# working.net
KiCad netlist of a schematic drawn in EAGLE
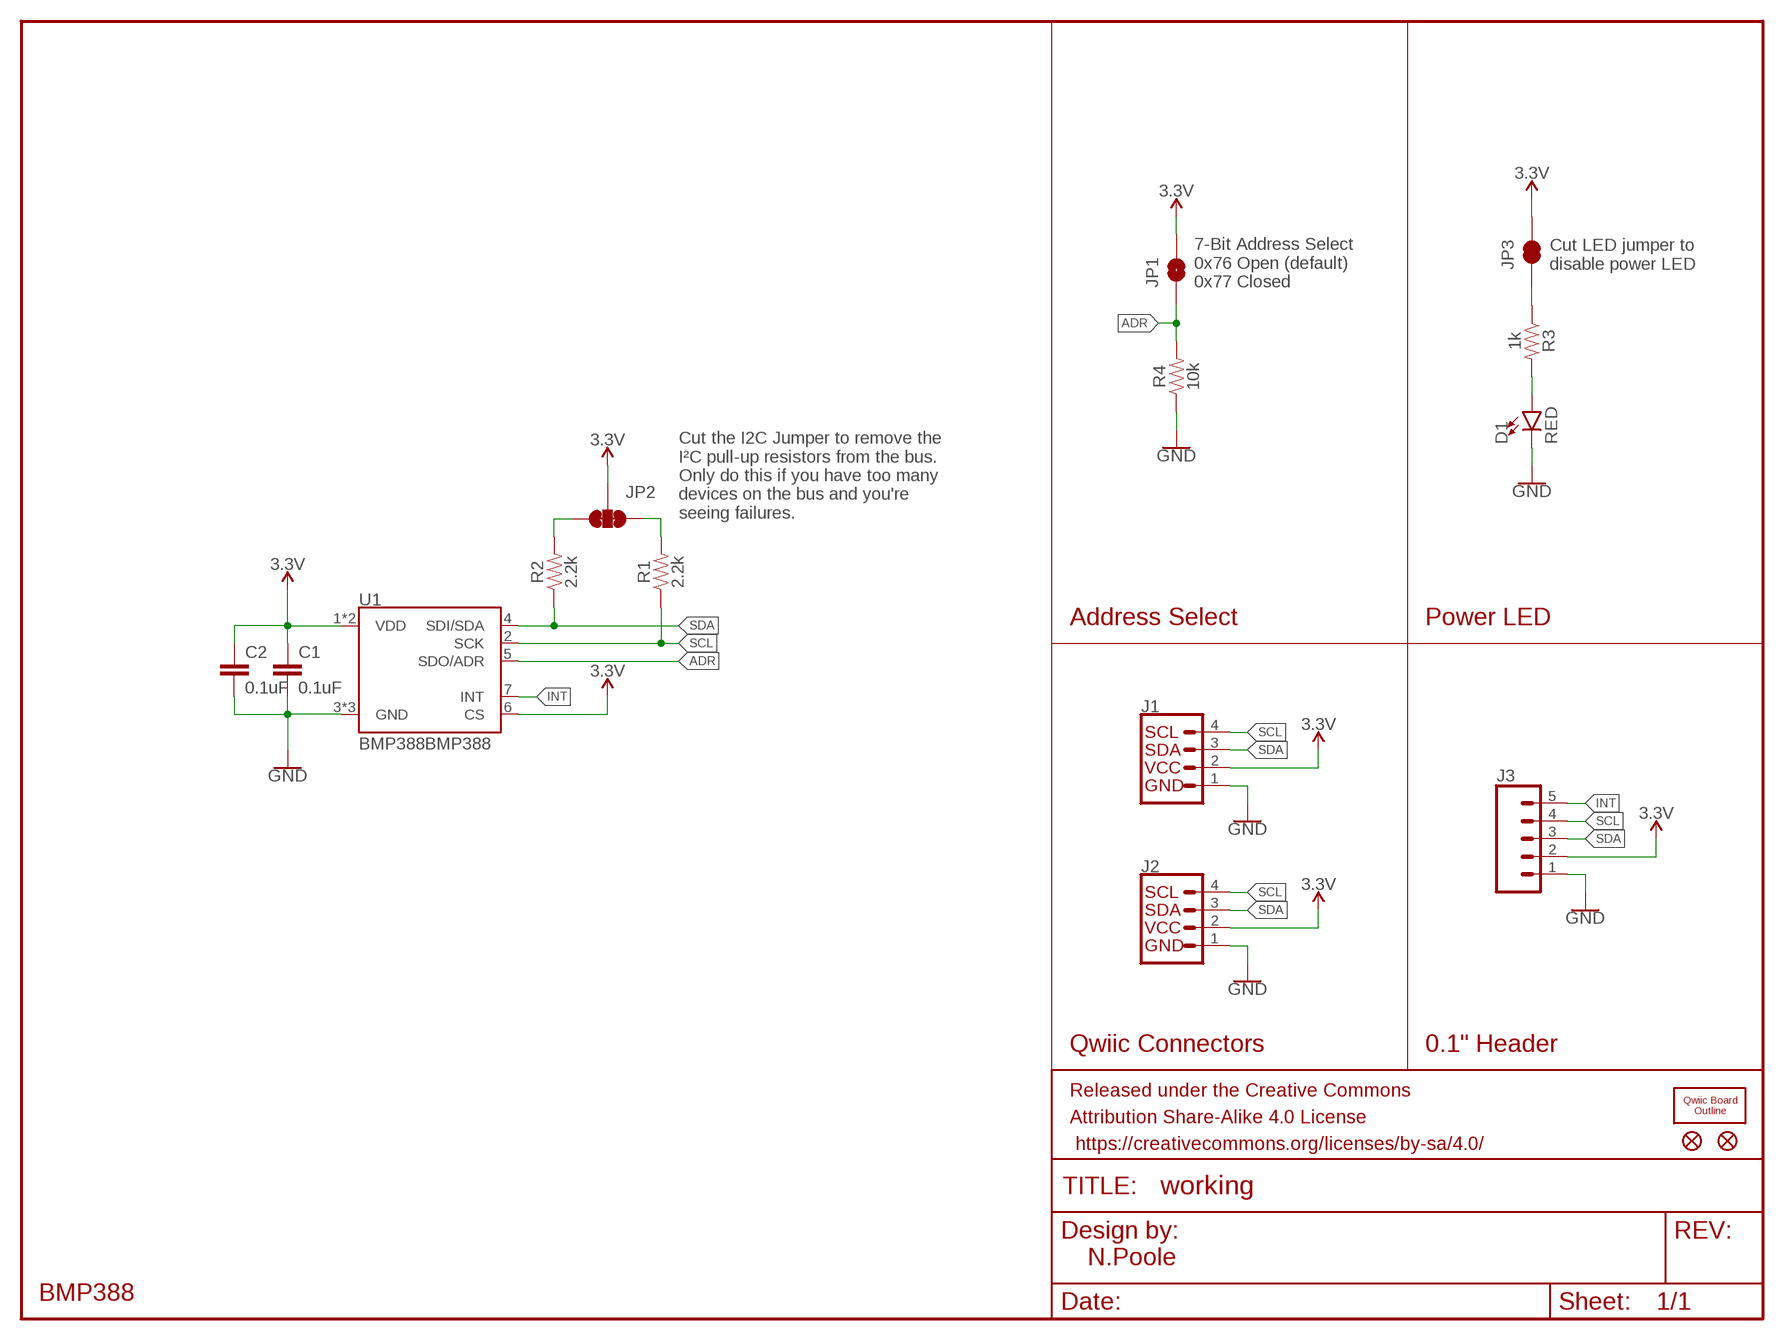
[diagram p0: schematic, sheet 1]

(export (version "E")
  (design (tool "Eeschema 10.0.6"))
  (components
    (comp (ref "A1")
      (value "QWIIC_BOARD_OUTLINEH")
      (footprint "eagle-import:QWIIC_BOARD_MOUNT_HOLES")
      (libsource (lib "eagle-import") (part "QWIIC_BOARD_OUTLINEH"))
    )
    (comp (ref "C1")
      (value "0.1uF")
      (footprint "eagle-import:0603")
      (libsource (lib "eagle-import") (part "0.1UF-0603-25V-(+80/-20%)"))
    )
    (comp (ref "C2")
      (value "0.1uF")
      (footprint "eagle-import:0603")
      (libsource (lib "eagle-import") (part "0.1UF-0603-25V-(+80/-20%)"))
    )
    (comp (ref "D1")
      (value "RED")
      (footprint "eagle-import:LED-0603")
      (libsource (lib "eagle-import") (part "LED-RED0603"))
    )
    (comp (ref "FD1")
      (value "FIDUCIALUFIDUCIAL")
      (footprint "eagle-import:FIDUCIAL-MICRO")
      (libsource (lib "eagle-import") (part "FIDUCIALUFIDUCIAL"))
    )
    (comp (ref "FD2")
      (value "FIDUCIALUFIDUCIAL")
      (footprint "eagle-import:FIDUCIAL-MICRO")
      (libsource (lib "eagle-import") (part "FIDUCIALUFIDUCIAL"))
    )
    (comp (ref "FRAME1")
      (value "FRAME-LETTERNO_PACKAGE")
      (footprint "eagle-import:DUMMY")
      (fields (field (name "DESIGNER") "Nobody"))
      (libsource (lib "eagle-import") (part "FRAME-LETTERNO_PACKAGE"))
    )
    (comp (ref "J1")
      (value "QWIIC_CONNECTORJS-1MM")
      (footprint "eagle-import:1X04_1MM_RA")
      (libsource (lib "eagle-import") (part "QWIIC_CONNECTORJS-1MM"))
    )
    (comp (ref "J2")
      (value "QWIIC_CONNECTORJS-1MM")
      (footprint "eagle-import:1X04_1MM_RA")
      (libsource (lib "eagle-import") (part "QWIIC_CONNECTORJS-1MM"))
    )
    (comp (ref "J3")
      (value "CONN_05NO_SILK")
      (footprint "eagle-import:1X05_NO_SILK")
      (libsource (lib "eagle-import") (part "CONN_05NO_SILK"))
    )
    (comp (ref "JP1")
      (value "JUMPER-SMT_2_NO_SILK")
      (footprint "eagle-import:SMT-JUMPER_2_NO_SILK")
      (libsource (lib "eagle-import") (part "JUMPER-SMT_2_NO_SILK"))
    )
    (comp (ref "JP2")
      (value "JUMPER-SMT_3_2-NC_TRACE_SILK")
      (footprint "eagle-import:SMT-JUMPER_3_2-NC_TRACE_SILK")
      (libsource (lib "eagle-import") (part "JUMPER-SMT_3_2-NC_TRACE_SILK"))
    )
    (comp (ref "JP3")
      (value "JUMPER-SMT_2_NC_TRACE_SILK")
      (footprint "eagle-import:SMT-JUMPER_2_NC_TRACE_SILK")
      (libsource (lib "eagle-import") (part "JUMPER-SMT_2_NC_TRACE_SILK"))
    )
    (comp (ref "R1")
      (value "2.2k")
      (footprint "eagle-import:0603")
      (libsource (lib "eagle-import") (part "2.2KOHM-0603-1/10W-1%"))
    )
    (comp (ref "R2")
      (value "2.2k")
      (footprint "eagle-import:0603")
      (libsource (lib "eagle-import") (part "2.2KOHM-0603-1/10W-1%"))
    )
    (comp (ref "R3")
      (value "1k")
      (footprint "eagle-import:0603")
      (libsource (lib "eagle-import") (part "1KOHM-0603-1/10W-1%"))
    )
    (comp (ref "R4")
      (value "10k")
      (footprint "eagle-import:0603")
      (libsource (lib "eagle-import") (part "10KOHM-0603-1/10W-1%"))
    )
    (comp (ref "U1")
      (value "BMP388BMP388")
      (footprint "eagle-import:LGA-10(2X2)")
      (libsource (lib "eagle-import") (part "BMP388BMP388"))
    )
  )
  (nets
    (net (code "1") (name "3.3V") (class "Default")
      (node (ref "C1") (pin "1") (pinfunction "1_1") (pintype "passive"))
      (node (ref "C2") (pin "1") (pinfunction "1_1") (pintype "passive"))
      (node (ref "J1") (pin "2") (pinfunction "VCC_2") (pintype "power_in"))
      (node (ref "J2") (pin "2") (pinfunction "VCC_2") (pintype "power_in"))
      (node (ref "J3") (pin "2") (pinfunction "2_2") (pintype "passive"))
      (node (ref "JP1") (pin "2") (pinfunction "2_2") (pintype "passive"))
      (node (ref "JP2") (pin "2") (pinfunction "2_2") (pintype "passive"))
      (node (ref "JP3") (pin "2") (pinfunction "2_2") (pintype "passive"))
      (node (ref "U1") (pin "1") (pinfunction "VDD_1") (pintype "bidirectional"))
      (node (ref "U1") (pin "10") (pinfunction "VDD_10") (pintype "bidirectional"))
      (node (ref "U1") (pin "6") (pinfunction "CS_6") (pintype "bidirectional"))
    )
    (net (code "2") (name "ADR") (class "Default")
      (node (ref "JP1") (pin "1") (pinfunction "1_1") (pintype "passive"))
      (node (ref "R4") (pin "2") (pinfunction "2_2") (pintype "passive"))
      (node (ref "U1") (pin "5") (pinfunction "SDO/ADR_5") (pintype "bidirectional"))
    )
    (net (code "3") (name "GND") (class "Default")
      (node (ref "C1") (pin "2") (pinfunction "2_2") (pintype "passive"))
      (node (ref "C2") (pin "2") (pinfunction "2_2") (pintype "passive"))
      (node (ref "D1") (pin "C") (pinfunction "C_C") (pintype "passive"))
      (node (ref "J1") (pin "1") (pinfunction "GND_1") (pintype "power_in"))
      (node (ref "J2") (pin "1") (pinfunction "GND_1") (pintype "power_in"))
      (node (ref "J3") (pin "1") (pinfunction "1_1") (pintype "passive"))
      (node (ref "R4") (pin "1") (pinfunction "1_1") (pintype "passive"))
      (node (ref "U1") (pin "3") (pinfunction "GND_3") (pintype "bidirectional"))
      (node (ref "U1") (pin "8") (pinfunction "GND_8") (pintype "bidirectional"))
      (node (ref "U1") (pin "9") (pinfunction "GND_9") (pintype "bidirectional"))
    )
    (net (code "4") (name "INT") (class "Default")
      (node (ref "J3") (pin "5") (pinfunction "5_5") (pintype "passive"))
      (node (ref "U1") (pin "7") (pinfunction "INT_7") (pintype "bidirectional"))
    )
    (net (code "5") (name "Net-(D1-PadA)") (class "Default")
      (node (ref "D1") (pin "A") (pinfunction "A_A") (pintype "passive"))
      (node (ref "R3") (pin "2") (pinfunction "2_2") (pintype "passive"))
    )
    (net (code "6") (name "Net-(JP2-Pad1)") (class "Default")
      (node (ref "JP2") (pin "1") (pinfunction "1_1") (pintype "passive"))
      (node (ref "R1") (pin "2") (pinfunction "2_2") (pintype "passive"))
    )
    (net (code "7") (name "Net-(JP2-Pad3)") (class "Default")
      (node (ref "JP2") (pin "3") (pinfunction "3_3") (pintype "passive"))
      (node (ref "R2") (pin "2") (pinfunction "2_2") (pintype "passive"))
    )
    (net (code "8") (name "Net-(JP3-Pad1)") (class "Default")
      (node (ref "JP3") (pin "1") (pinfunction "1_1") (pintype "passive"))
      (node (ref "R3") (pin "1") (pinfunction "1_1") (pintype "passive"))
    )
    (net (code "9") (name "SCL") (class "Default")
      (node (ref "J1") (pin "4") (pinfunction "SCL_4") (pintype "passive"))
      (node (ref "J2") (pin "4") (pinfunction "SCL_4") (pintype "passive"))
      (node (ref "J3") (pin "4") (pinfunction "4_4") (pintype "passive"))
      (node (ref "R1") (pin "1") (pinfunction "1_1") (pintype "passive"))
      (node (ref "U1") (pin "2") (pinfunction "SCK_2") (pintype "bidirectional"))
    )
    (net (code "10") (name "SDA") (class "Default")
      (node (ref "J1") (pin "3") (pinfunction "SDA_3") (pintype "passive"))
      (node (ref "J2") (pin "3") (pinfunction "SDA_3") (pintype "passive"))
      (node (ref "J3") (pin "3") (pinfunction "3_3") (pintype "passive"))
      (node (ref "R2") (pin "1") (pinfunction "1_1") (pintype "passive"))
      (node (ref "U1") (pin "4") (pinfunction "SDI/SDA_4") (pintype "bidirectional"))
    )
  )
)
